# PCB_Schematic_Layout.net
KiCad netlist of a schematic drawn in EasyEDA
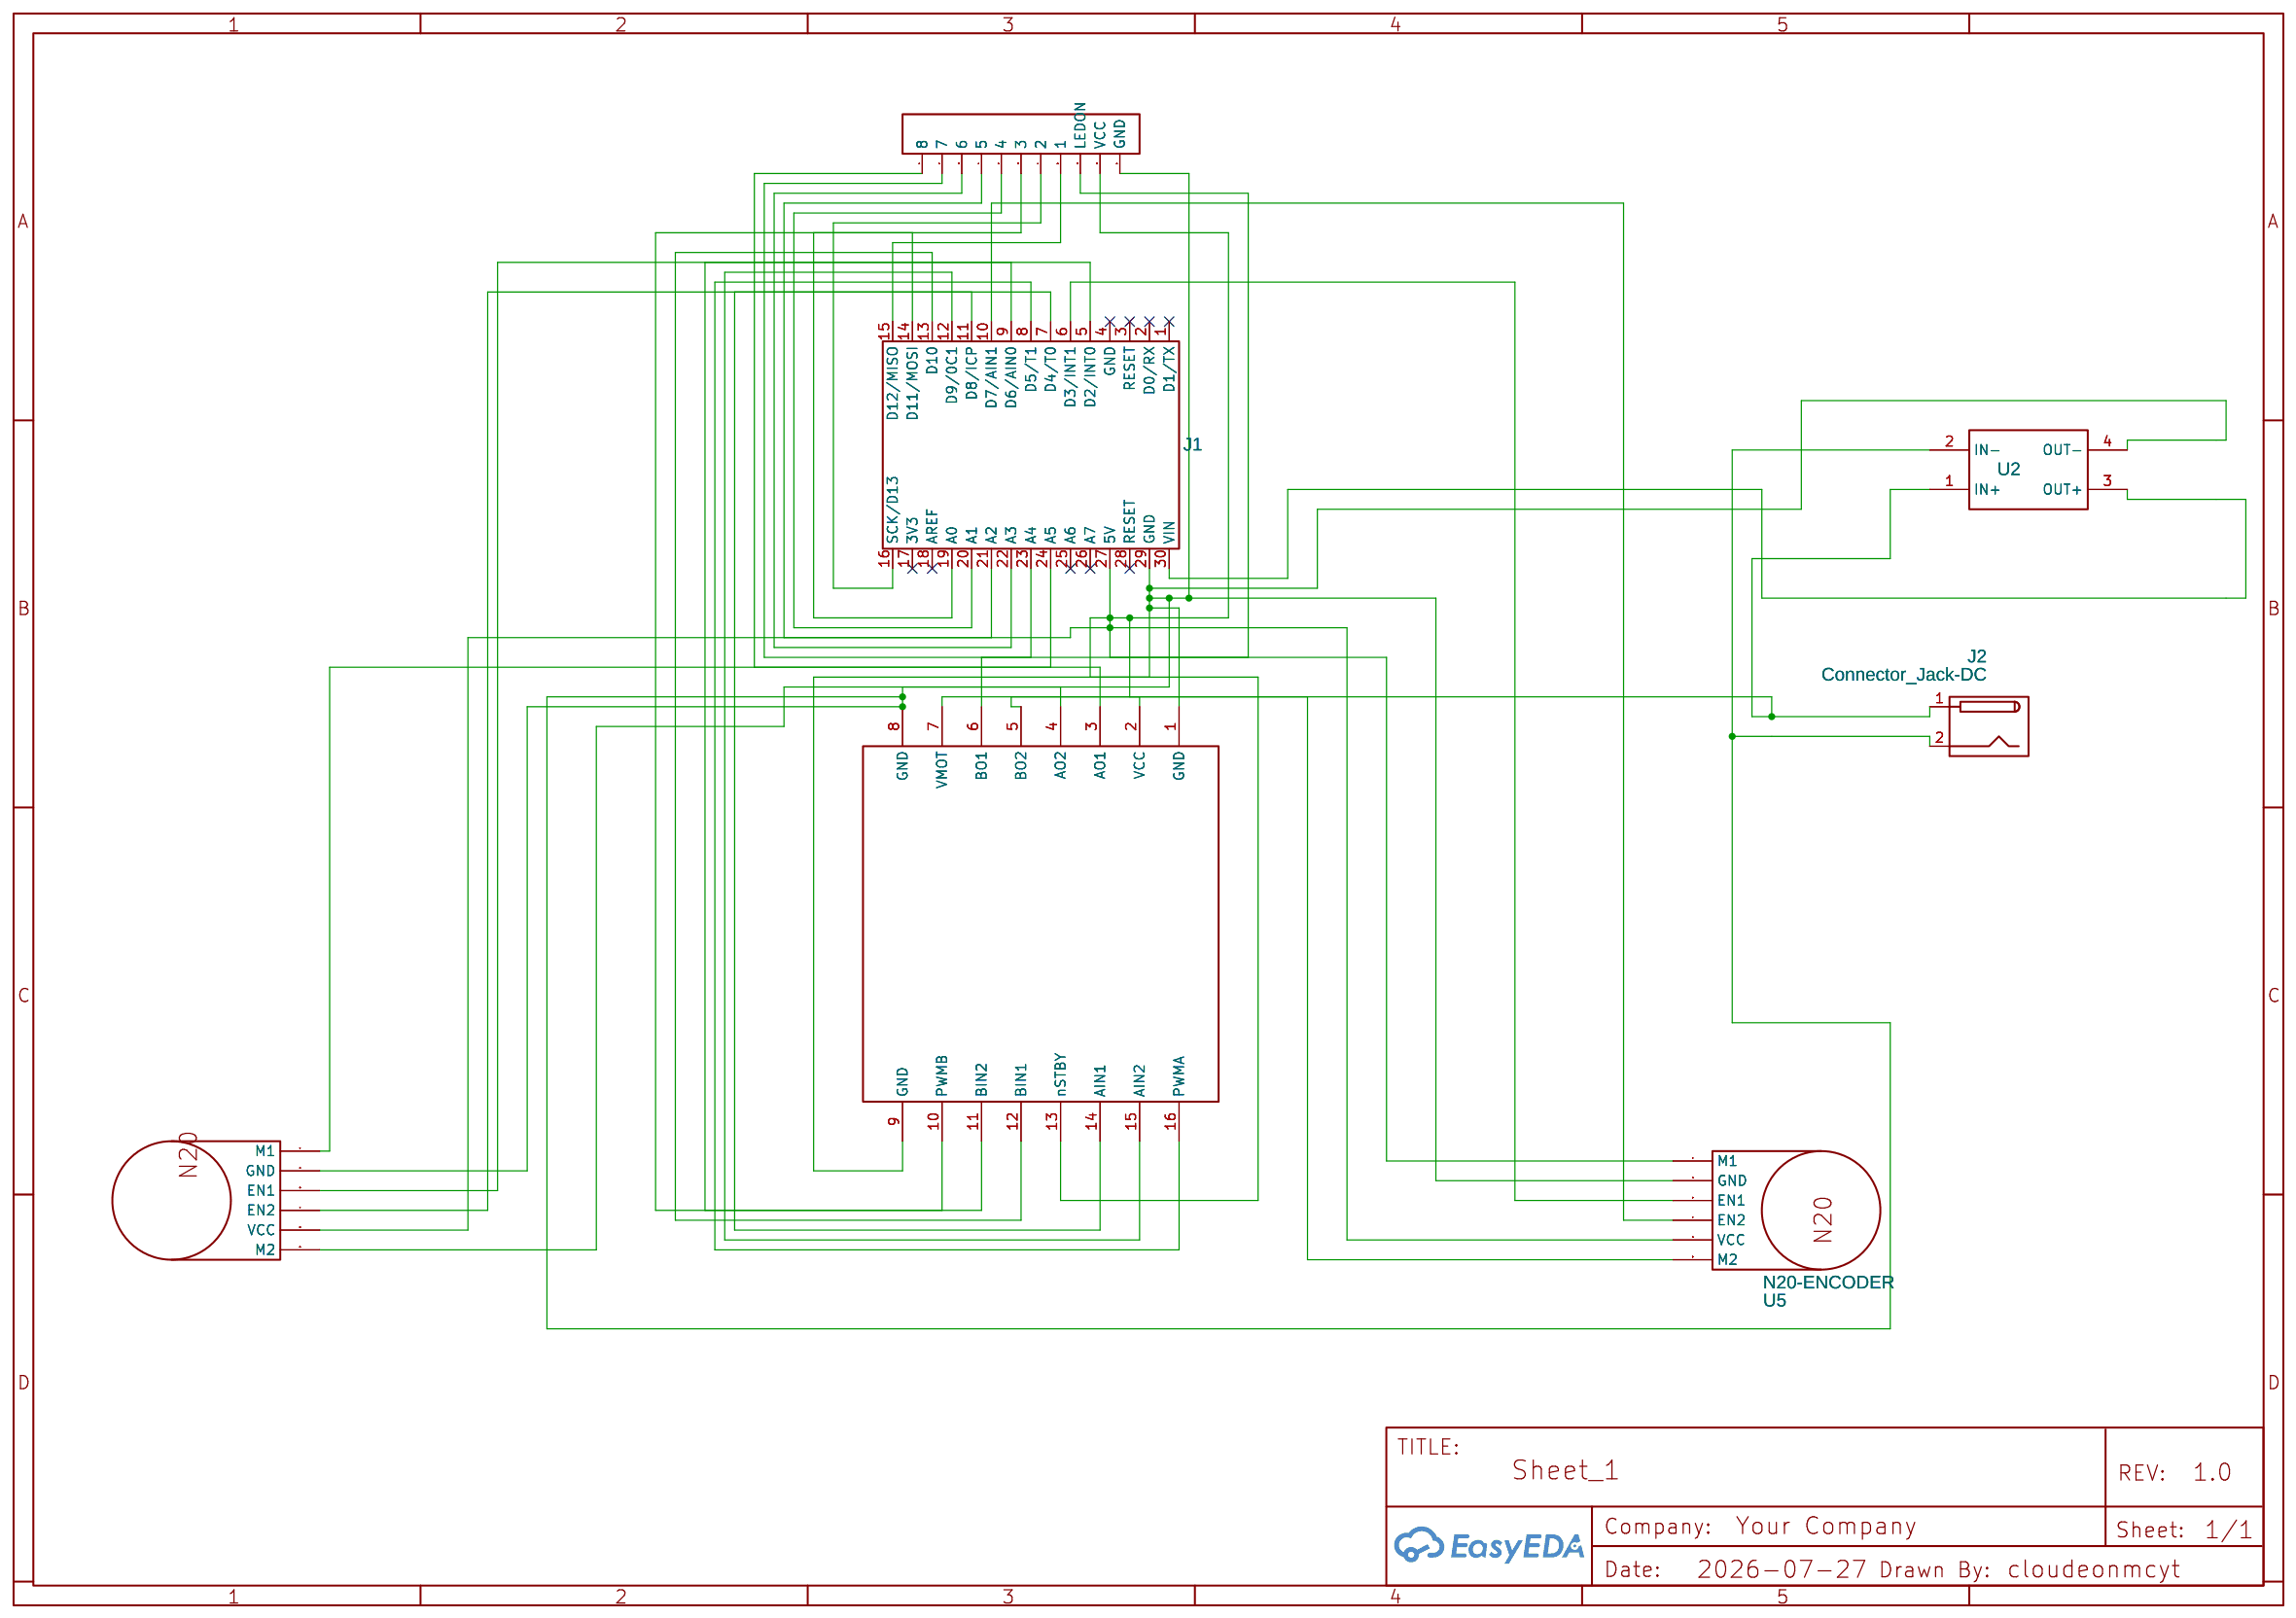
[diagram p0: schematic sheet]

(export (version "E")
  (design (tool "Eeschema 10.0.6"))
  (components
    (comp (ref "J1") (value "Arduino_Nano_Header") (libsource (lib "") (part "Arduino_Nano_Header")))
    (comp (ref "J2") (value "Connector_Jack-DC") (libsource (lib "") (part "Connector_Jack-DC")))
    (comp (ref "P1") (value "Header-Female-2.54_1x11") (libsource (lib "") (part "Header-Female-2.54_1x11")))
    (comp (ref "U1")
      (value "TB6612FNG Dual Motor Driver Carrier")
      (libsource (lib "") (part "TB6612FNG Dual Motor Driver Carrier"))
    )
    (comp (ref "U2") (value "MP1584EN") (libsource (lib "") (part "MP1584EN")))
    (comp (ref "U5") (value "N20-ENCODER") (libsource (lib "") (part "N20-ENCODER")))
    (comp (ref "U6") (value "N20-ENCODER") (libsource (lib "") (part "N20-ENCODER_1")))
  )
  (nets
    (net (code "1") (name "Net-(J1-5V)") (class "Default")
      (node (ref "J1") (pin "27") (pinfunction "5V_27") (pintype "unspecified"))
      (node (ref "P1") (pin "10") (pinfunction "VCC_10") (pintype "input"))
      (node (ref "P1") (pin "9") (pinfunction "LEDON_9") (pintype "input"))
      (node (ref "U1") (pin "13") (pinfunction "nSTBY_13") (pintype "unspecified"))
      (node (ref "U1") (pin "2") (pinfunction "VCC_2") (pintype "unspecified"))
      (node (ref "U5") (pin "5") (pinfunction "VCC_5") (pintype "unspecified"))
      (node (ref "U6") (pin "5") (pinfunction "VCC_5") (pintype "unspecified"))
    )
    (net (code "2") (name "Net-(J1-A0)") (class "Default")
      (node (ref "J1") (pin "19") (pinfunction "A0_19") (pintype "unspecified"))
      (node (ref "P1") (pin "6") (pinfunction "3_6") (pintype "input"))
    )
    (net (code "3") (name "Net-(J1-A1)") (class "Default")
      (node (ref "J1") (pin "20") (pinfunction "A1_20") (pintype "unspecified"))
      (node (ref "P1") (pin "5") (pinfunction "4_5") (pintype "input"))
    )
    (net (code "4") (name "Net-(J1-A2)") (class "Default")
      (node (ref "J1") (pin "21") (pinfunction "A2_21") (pintype "unspecified"))
      (node (ref "P1") (pin "4") (pinfunction "5_4") (pintype "input"))
    )
    (net (code "5") (name "Net-(J1-A3)") (class "Default")
      (node (ref "J1") (pin "22") (pinfunction "A3_22") (pintype "unspecified"))
      (node (ref "P1") (pin "3") (pinfunction "6_3") (pintype "input"))
    )
    (net (code "6") (name "Net-(J1-A4)") (class "Default")
      (node (ref "J1") (pin "23") (pinfunction "A4_23") (pintype "unspecified"))
      (node (ref "P1") (pin "2") (pinfunction "7_2") (pintype "input"))
    )
    (net (code "7") (name "Net-(J1-A5)") (class "Default")
      (node (ref "J1") (pin "24") (pinfunction "A5_24") (pintype "unspecified"))
      (node (ref "P1") (pin "1") (pinfunction "8_1") (pintype "input"))
    )
    (net (code "8") (name "Net-(J1-D2{slash}INT0)") (class "Default")
      (node (ref "J1") (pin "5") (pinfunction "D2/INT0_5") (pintype "unspecified"))
      (node (ref "U6") (pin "3") (pinfunction "EN1_3") (pintype "unspecified"))
    )
    (net (code "9") (name "Net-(J1-D3{slash}INT1)") (class "Default")
      (node (ref "J1") (pin "6") (pinfunction "D3/INT1_6") (pintype "unspecified"))
      (node (ref "U5") (pin "3") (pinfunction "EN1_3") (pintype "unspecified"))
    )
    (net (code "10") (name "Net-(J1-D4{slash}T0)") (class "Default")
      (node (ref "J1") (pin "7") (pinfunction "D4/T0_7") (pintype "unspecified"))
      (node (ref "U6") (pin "4") (pinfunction "EN2_4") (pintype "unspecified"))
    )
    (net (code "11") (name "Net-(J1-D5{slash}T1)") (class "Default")
      (node (ref "J1") (pin "8") (pinfunction "D5/T1_8") (pintype "unspecified"))
      (node (ref "U1") (pin "16") (pinfunction "PWMA_16") (pintype "unspecified"))
    )
    (net (code "12") (name "Net-(J1-D6{slash}AIN0)") (class "Default")
      (node (ref "J1") (pin "9") (pinfunction "D6/AIN0_9") (pintype "unspecified"))
      (node (ref "U1") (pin "10") (pinfunction "PWMB_10") (pintype "unspecified"))
    )
    (net (code "13") (name "Net-(J1-D7{slash}AIN1)") (class "Default")
      (node (ref "J1") (pin "10") (pinfunction "D7/AIN1_10") (pintype "unspecified"))
      (node (ref "U5") (pin "4") (pinfunction "EN2_4") (pintype "unspecified"))
    )
    (net (code "14") (name "Net-(J1-D8{slash}ICP)") (class "Default")
      (node (ref "J1") (pin "11") (pinfunction "D8/ICP_11") (pintype "unspecified"))
      (node (ref "U1") (pin "14") (pinfunction "AIN1_14") (pintype "unspecified"))
    )
    (net (code "15") (name "Net-(J1-D9{slash}0C1)") (class "Default")
      (node (ref "J1") (pin "12") (pinfunction "D9/0C1_12") (pintype "unspecified"))
      (node (ref "U1") (pin "15") (pinfunction "AIN2_15") (pintype "unspecified"))
    )
    (net (code "16") (name "Net-(J1-D10)") (class "Default")
      (node (ref "J1") (pin "13") (pinfunction "D10_13") (pintype "unspecified"))
      (node (ref "U1") (pin "12") (pinfunction "BIN1_12") (pintype "unspecified"))
    )
    (net (code "17") (name "Net-(J1-D11{slash}MOSI)") (class "Default")
      (node (ref "J1") (pin "14") (pinfunction "D11/MOSI_14") (pintype "unspecified"))
      (node (ref "U1") (pin "11") (pinfunction "BIN2_11") (pintype "unspecified"))
    )
    (net (code "18") (name "Net-(J1-D12{slash}MISO)") (class "Default")
      (node (ref "J1") (pin "15") (pinfunction "D12/MISO_15") (pintype "unspecified"))
      (node (ref "P1") (pin "8") (pinfunction "1_8") (pintype "input"))
    )
    (net (code "19") (name "Net-(J1-SCK{slash}D13)") (class "Default")
      (node (ref "J1") (pin "16") (pinfunction "SCK/D13_16") (pintype "unspecified"))
      (node (ref "P1") (pin "7") (pinfunction "2_7") (pintype "input"))
    )
    (net (code "20") (name "Net-(J1-VIN)") (class "Default")
      (node (ref "J1") (pin "30") (pinfunction "VIN_30") (pintype "unspecified"))
      (node (ref "U2") (pin "3") (pinfunction "OUT+_3") (pintype "unspecified"))
    )
    (net (code "21") (name "Net-(P1-GND)") (class "Default")
      (node (ref "J1") (pin "29") (pinfunction "GND_29") (pintype "unspecified"))
      (node (ref "J2") (pin "2") (pintype "unspecified"))
      (node (ref "P1") (pin "11") (pinfunction "GND_11") (pintype "input"))
      (node (ref "U1") (pin "1") (pinfunction "GND_1") (pintype "unspecified"))
      (node (ref "U1") (pin "8") (pinfunction "GND_8") (pintype "unspecified"))
      (node (ref "U1") (pin "9") (pinfunction "GND_9") (pintype "unspecified"))
      (node (ref "U2") (pin "2") (pinfunction "IN-_2") (pintype "unspecified"))
      (node (ref "U2") (pin "4") (pinfunction "OUT-_4") (pintype "unspecified"))
      (node (ref "U5") (pin "2") (pinfunction "GND_2") (pintype "unspecified"))
      (node (ref "U6") (pin "2") (pinfunction "GND_2") (pintype "unspecified"))
    )
    (net (code "22") (name "Net-(U1-AO1)") (class "Default")
      (node (ref "U1") (pin "3") (pinfunction "AO1_3") (pintype "unspecified"))
      (node (ref "U6") (pin "1") (pinfunction "M1_1") (pintype "unspecified"))
    )
    (net (code "23") (name "Net-(U1-AO2)") (class "Default")
      (node (ref "U1") (pin "4") (pinfunction "AO2_4") (pintype "unspecified"))
      (node (ref "U6") (pin "6") (pinfunction "M2_6") (pintype "unspecified"))
    )
    (net (code "24") (name "Net-(U1-BO1)") (class "Default")
      (node (ref "U1") (pin "6") (pinfunction "BO1_6") (pintype "unspecified"))
      (node (ref "U5") (pin "1") (pinfunction "M1_1") (pintype "unspecified"))
    )
    (net (code "25") (name "Net-(U1-BO2)") (class "Default")
      (node (ref "U1") (pin "5") (pinfunction "BO2_5") (pintype "unspecified"))
      (node (ref "U5") (pin "6") (pinfunction "M2_6") (pintype "unspecified"))
    )
    (net (code "26") (name "Net-(U1-VMOT)") (class "Default")
      (node (ref "J2") (pin "1") (pintype "unspecified"))
      (node (ref "U1") (pin "7") (pinfunction "VMOT_7") (pintype "unspecified"))
      (node (ref "U2") (pin "1") (pinfunction "IN+_1") (pintype "unspecified"))
    )
    (net (code "27") (name "unconnected-(J1-3V3-Pad17)") (class "Default")
      (node (ref "J1") (pin "17") (pinfunction "3V3_17") (pintype "unspecified+no_connect"))
    )
    (net (code "28") (name "unconnected-(J1-A6-Pad25)") (class "Default")
      (node (ref "J1") (pin "25") (pinfunction "A6_25") (pintype "unspecified+no_connect"))
    )
    (net (code "29") (name "unconnected-(J1-A7-Pad26)") (class "Default")
      (node (ref "J1") (pin "26") (pinfunction "A7_26") (pintype "unspecified+no_connect"))
    )
    (net (code "30") (name "unconnected-(J1-AREF-Pad18)") (class "Default")
      (node (ref "J1") (pin "18") (pinfunction "AREF_18") (pintype "unspecified+no_connect"))
    )
    (net (code "31") (name "unconnected-(J1-D0{slash}RX-Pad2)") (class "Default")
      (node (ref "J1") (pin "2") (pinfunction "D0/RX_2") (pintype "unspecified+no_connect"))
    )
    (net (code "32") (name "unconnected-(J1-D1{slash}TX-Pad1)") (class "Default")
      (node (ref "J1") (pin "1") (pinfunction "D1/TX_1") (pintype "unspecified+no_connect"))
    )
    (net (code "33") (name "unconnected-(J1-GND-Pad4)") (class "Default")
      (node (ref "J1") (pin "4") (pinfunction "GND_4") (pintype "unspecified+no_connect"))
    )
    (net (code "34") (name "unconnected-(J1-RESET-Pad3)") (class "Default")
      (node (ref "J1") (pin "3") (pinfunction "RESET_3") (pintype "unspecified+no_connect"))
    )
    (net (code "35") (name "unconnected-(J1-RESET-Pad28)") (class "Default")
      (node (ref "J1") (pin "28") (pinfunction "RESET_28") (pintype "unspecified+no_connect"))
    )
  )
)
